# SpaceInvaders-OtherMill-DoubleSided.net
KiCad netlist of a schematic drawn in EAGLE
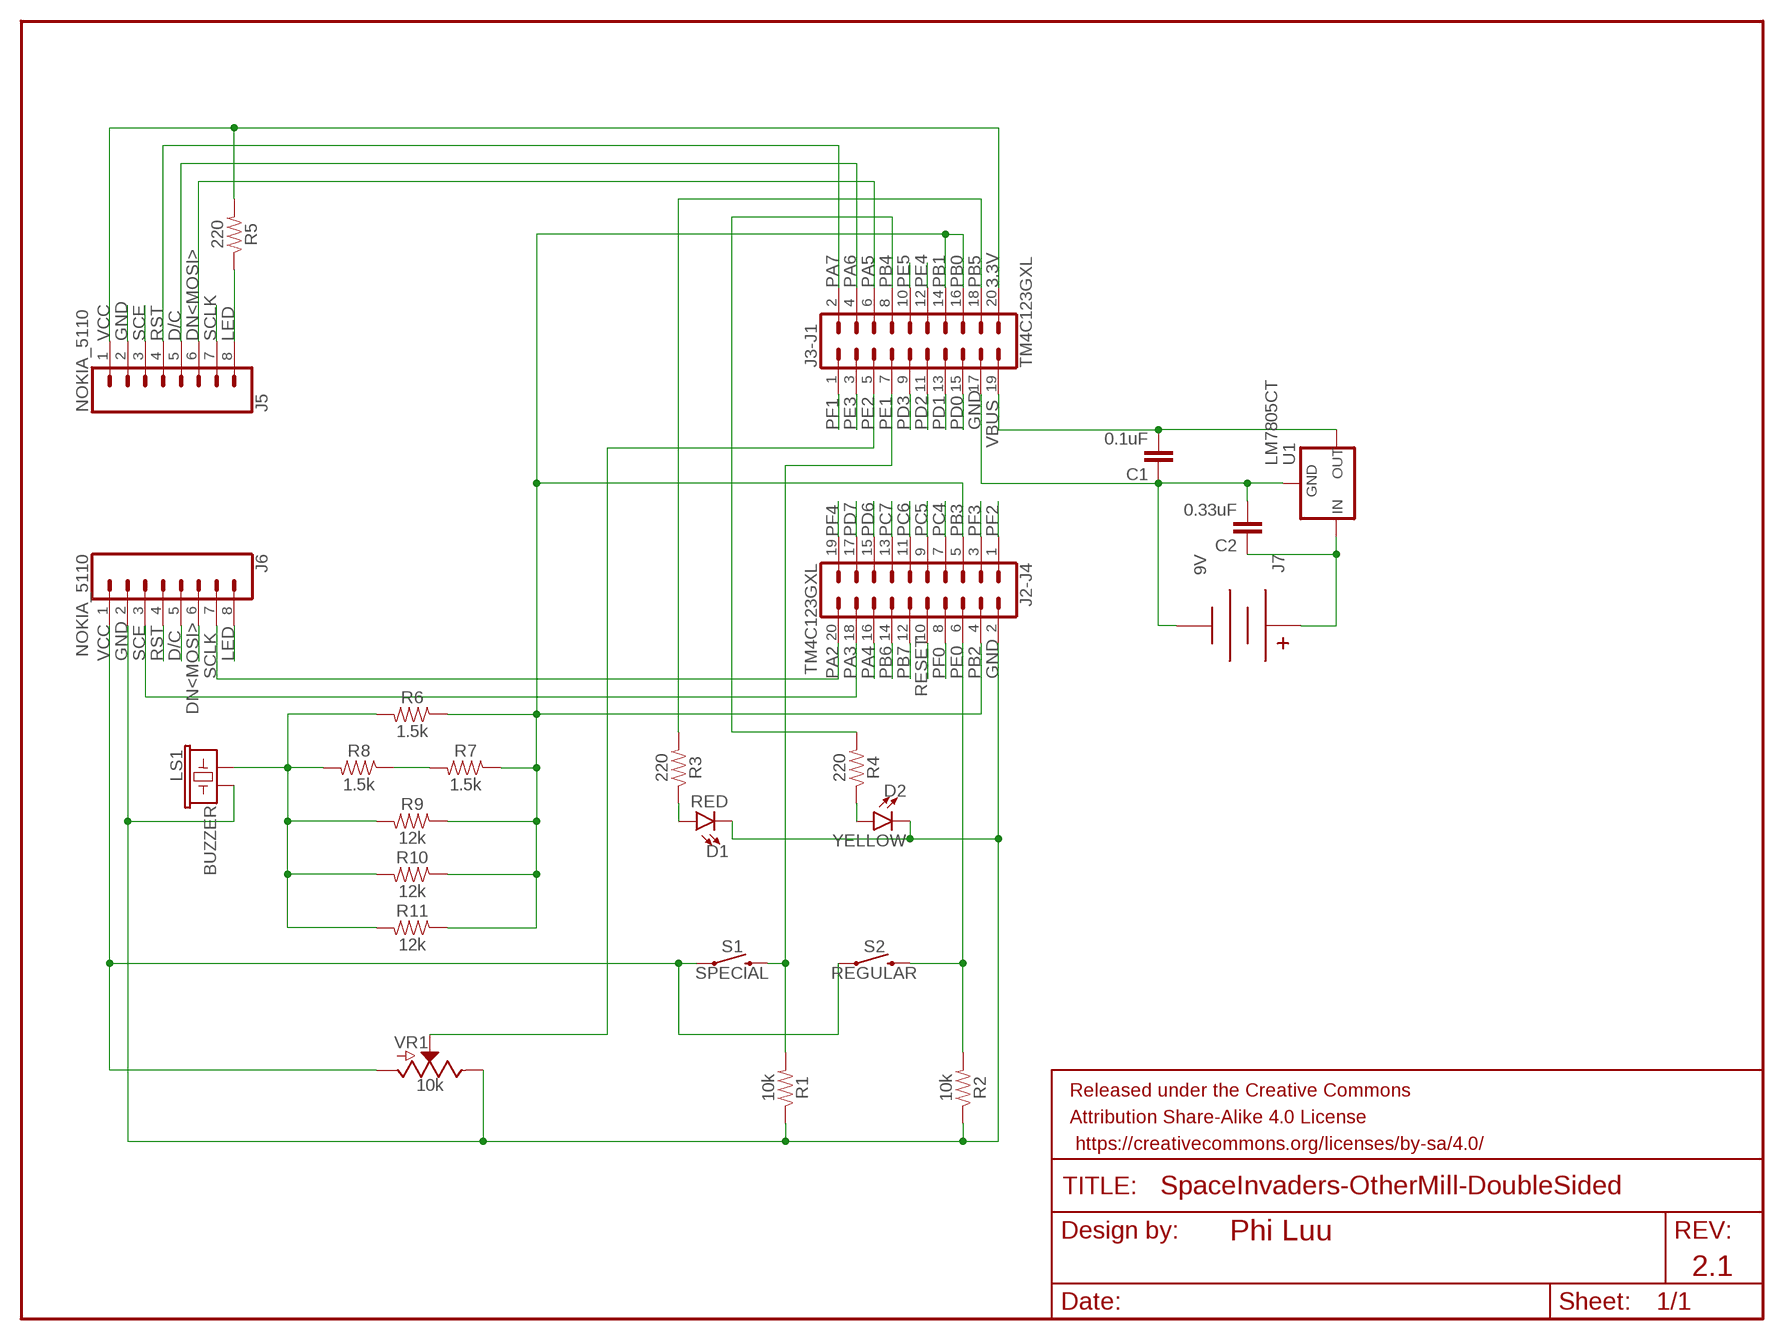
[diagram p0: schematic, sheet 1]

(export (version "E")
  (design (tool "Eeschema 10.0.6"))
  (components
    (comp (ref "C1")
      (value "0.1uF")
      (footprint "eagle-import:CAP-PTH-SMALL-KIT")
      (libsource (lib "eagle-import") (part "0.1UF-KIT-EZ-50V-20%"))
    )
    (comp (ref "C2")
      (value "0.33uF")
      (footprint "eagle-import:CAP-PTH-SMALL-KIT")
      (libsource (lib "eagle-import") (part "0.1UF-KIT-EZ-50V-20%"))
    )
    (comp (ref "D1")
      (value "RED")
      (footprint "eagle-import:LED_5MM")
      (libsource (lib "eagle-import") (part "LED5MM"))
    )
    (comp (ref "D2")
      (value "YELLOW")
      (footprint "eagle-import:LED_5MM")
      (libsource (lib "eagle-import") (part "LED5MM"))
    )
    (comp (ref "FRAME1")
      (value "FRAME-LETTER")
      (footprint "eagle-import:CREATIVE_COMMONS")
      (libsource (lib "eagle-import") (part "FRAME-LETTER"))
    )
    (comp (ref "J2-J4")
      (value "TM4C123GXL")
      (footprint "eagle-import:2X10")
      (libsource (lib "eagle-import") (part "CONN_10X2"))
    )
    (comp (ref "J3-J1")
      (value "TM4C123GXL")
      (footprint "eagle-import:2X10")
      (libsource (lib "eagle-import") (part "CONN_10X2"))
    )
    (comp (ref "J5")
      (value "NOKIA_5110")
      (footprint "eagle-import:1X08")
      (libsource (lib "eagle-import") (part "CONN_08{dblquote}"))
    )
    (comp (ref "J6")
      (value "NOKIA_5110")
      (footprint "eagle-import:1X08")
      (libsource (lib "eagle-import") (part "CONN_08{dblquote}"))
    )
    (comp (ref "J7")
      (value "9V")
      (footprint "eagle-import:BC9VPC")
      (libsource (lib "eagle-import") (part "BC9VPC"))
    )
    (comp (ref "LS1")
      (value "BUZZER")
      (footprint "eagle-import:BUZZER-12MM")
      (libsource (lib "eagle-import") (part "BUZZER-PTH"))
    )
    (comp (ref "R1")
      (value "10k")
      (footprint "eagle-import:AXIAL-0.3")
      (libsource (lib "eagle-import") (part "10KOHM-HORIZ-1/4W-5%"))
    )
    (comp (ref "R2")
      (value "10k")
      (footprint "eagle-import:AXIAL-0.3")
      (libsource (lib "eagle-import") (part "10KOHM-HORIZ-1/4W-5%"))
    )
    (comp (ref "R3")
      (value "220")
      (footprint "eagle-import:AXIAL-0.3")
      (libsource (lib "eagle-import") (part "1KOHM-HORIZ-1/4W-5%"))
    )
    (comp (ref "R4")
      (value "220")
      (footprint "eagle-import:AXIAL-0.3")
      (libsource (lib "eagle-import") (part "1KOHM-HORIZ-1/4W-5%"))
    )
    (comp (ref "R5")
      (value "220")
      (footprint "eagle-import:AXIAL-0.3")
      (libsource (lib "eagle-import") (part "1KOHM-HORIZ-1/4W-5%"))
    )
    (comp (ref "R6")
      (value "1.5k")
      (footprint "eagle-import:AXIAL-0.3")
      (libsource (lib "eagle-import") (part "1KOHM-HORIZ-1/4W-5%"))
    )
    (comp (ref "R7")
      (value "1.5k")
      (footprint "eagle-import:AXIAL-0.3")
      (libsource (lib "eagle-import") (part "1KOHM-HORIZ-1/4W-5%"))
    )
    (comp (ref "R8")
      (value "1.5k")
      (footprint "eagle-import:AXIAL-0.3")
      (libsource (lib "eagle-import") (part "1KOHM-HORIZ-1/4W-5%"))
    )
    (comp (ref "R9")
      (value "12k")
      (footprint "eagle-import:AXIAL-0.3")
      (libsource (lib "eagle-import") (part "1KOHM-HORIZ-1/4W-5%"))
    )
    (comp (ref "R10")
      (value "12k")
      (footprint "eagle-import:AXIAL-0.3")
      (libsource (lib "eagle-import") (part "1KOHM-HORIZ-1/4W-5%"))
    )
    (comp (ref "R11")
      (value "12k")
      (footprint "eagle-import:AXIAL-0.3")
      (libsource (lib "eagle-import") (part "1KOHM-HORIZ-1/4W-5%"))
    )
    (comp (ref "S1")
      (value "SPECIAL")
      (footprint "eagle-import:TACTILE_SWITCH_PTH_6.0MM")
      (libsource (lib "eagle-import") (part "MOMENTARY-SWITCH-SPST-PTH-6.0MM"))
    )
    (comp (ref "S2")
      (value "REGULAR")
      (footprint "eagle-import:TACTILE_SWITCH_PTH_6.0MM")
      (libsource (lib "eagle-import") (part "MOMENTARY-SWITCH-SPST-PTH-6.0MM"))
    )
    (comp (ref "U1")
      (value "LM7805CT")
      (footprint "eagle-import:TO-220-ALT")
      (libsource (lib "eagle-import") (part "V_REG_78XX-TO-220"))
    )
    (comp (ref "VR1")
      (value "10k")
      (footprint "eagle-import:SLIDER-MEDIUM")
      (libsource (lib "eagle-import") (part "POTENTIOMETER_SLIDE-30MM-1/10W-20%"))
    )
  )
  (nets
    (net (code "1") (name "/3.3V") (class "Default")
      (node (ref "J3-J1") (pin "20") (pinfunction "20_20") (pintype "passive"))
      (node (ref "J5") (pin "1") (pinfunction "1_1") (pintype "passive"))
      (node (ref "J6") (pin "1") (pinfunction "1_1") (pintype "passive"))
      (node (ref "R5") (pin "P$2") (pinfunction "2_P$2") (pintype "passive"))
      (node (ref "S1") (pin "1") (pinfunction "1_1") (pintype "passive"))
      (node (ref "S2") (pin "1") (pinfunction "1_1") (pintype "passive"))
      (node (ref "VR1") (pin "BOTTOM") (pinfunction "A_BOTTOM") (pintype "passive"))
    )
    (net (code "2") (name "/GND") (class "Default")
      (node (ref "C1") (pin "1") (pinfunction "1_1") (pintype "passive"))
      (node (ref "C2") (pin "2") (pinfunction "2_2") (pintype "passive"))
      (node (ref "D1") (pin "K") (pinfunction "C_K") (pintype "passive"))
      (node (ref "D2") (pin "K") (pinfunction "C_K") (pintype "passive"))
      (node (ref "J2-J4") (pin "2") (pinfunction "2_2") (pintype "passive"))
      (node (ref "J3-J1") (pin "17") (pinfunction "17_17") (pintype "passive"))
      (node (ref "J5") (pin "2") (pinfunction "2_2") (pintype "passive"))
      (node (ref "J6") (pin "2") (pinfunction "2_2") (pintype "passive"))
      (node (ref "J7") (pin "V-") (pinfunction "V-_V-") (pintype "bidirectional"))
      (node (ref "LS1") (pin "-") (pinfunction "2_-") (pintype "passive"))
      (node (ref "R1") (pin "P$1") (pinfunction "1_P$1") (pintype "passive"))
      (node (ref "R2") (pin "P$1") (pinfunction "1_P$1") (pintype "passive"))
      (node (ref "U1") (pin "GND") (pinfunction "GND_GND") (pintype "input"))
      (node (ref "VR1") (pin "TOP") (pinfunction "E_TOP") (pintype "passive"))
    )
    (net (code "3") (name "/LED") (class "Default")
      (node (ref "J5") (pin "8") (pinfunction "8_8") (pintype "passive"))
      (node (ref "J6") (pin "8") (pinfunction "8_8") (pintype "passive"))
      (node (ref "R5") (pin "P$1") (pinfunction "1_P$1") (pintype "passive"))
    )
    (net (code "4") (name "/PA2") (class "Default")
      (node (ref "J2-J4") (pin "20") (pinfunction "20_20") (pintype "passive"))
      (node (ref "J5") (pin "7") (pinfunction "7_7") (pintype "passive"))
      (node (ref "J6") (pin "7") (pinfunction "7_7") (pintype "passive"))
    )
    (net (code "5") (name "/PA3") (class "Default")
      (node (ref "J2-J4") (pin "18") (pinfunction "18_18") (pintype "passive"))
      (node (ref "J5") (pin "3") (pinfunction "3_3") (pintype "passive"))
      (node (ref "J6") (pin "3") (pinfunction "3_3") (pintype "passive"))
    )
    (net (code "6") (name "/PA4") (class "Default")
      (node (ref "J2-J4") (pin "16") (pinfunction "16_16") (pintype "passive"))
    )
    (net (code "7") (name "/PA5") (class "Default")
      (node (ref "J3-J1") (pin "6") (pinfunction "6_6") (pintype "passive"))
      (node (ref "J5") (pin "6") (pinfunction "6_6") (pintype "passive"))
      (node (ref "J6") (pin "6") (pinfunction "6_6") (pintype "passive"))
    )
    (net (code "8") (name "/PA6") (class "Default")
      (node (ref "J3-J1") (pin "4") (pinfunction "4_4") (pintype "passive"))
      (node (ref "J5") (pin "5") (pinfunction "5_5") (pintype "passive"))
      (node (ref "J6") (pin "5") (pinfunction "5_5") (pintype "passive"))
    )
    (net (code "9") (name "/PA7") (class "Default")
      (node (ref "J3-J1") (pin "2") (pinfunction "2_2") (pintype "passive"))
      (node (ref "J5") (pin "4") (pinfunction "4_4") (pintype "passive"))
      (node (ref "J6") (pin "4") (pinfunction "4_4") (pintype "passive"))
    )
    (net (code "10") (name "/PB4") (class "Default")
      (node (ref "J3-J1") (pin "8") (pinfunction "8_8") (pintype "passive"))
      (node (ref "R4") (pin "P$2") (pinfunction "2_P$2") (pintype "passive"))
    )
    (net (code "11") (name "/PB5") (class "Default")
      (node (ref "J3-J1") (pin "18") (pinfunction "18_18") (pintype "passive"))
      (node (ref "R3") (pin "P$2") (pinfunction "2_P$2") (pintype "passive"))
    )
    (net (code "12") (name "/PB6") (class "Default")
      (node (ref "J2-J4") (pin "14") (pinfunction "14_14") (pintype "passive"))
    )
    (net (code "13") (name "/PB7") (class "Default")
      (node (ref "J2-J4") (pin "12") (pinfunction "12_12") (pintype "passive"))
    )
    (net (code "14") (name "/PC4") (class "Default")
      (node (ref "J2-J4") (pin "7") (pinfunction "7_7") (pintype "passive"))
    )
    (net (code "15") (name "/PC5") (class "Default")
      (node (ref "J2-J4") (pin "9") (pinfunction "9_9") (pintype "passive"))
    )
    (net (code "16") (name "/PC6") (class "Default")
      (node (ref "J2-J4") (pin "11") (pinfunction "11_11") (pintype "passive"))
    )
    (net (code "17") (name "/PC7") (class "Default")
      (node (ref "J2-J4") (pin "13") (pinfunction "13_13") (pintype "passive"))
    )
    (net (code "18") (name "/PD0") (class "Default")
      (node (ref "J3-J1") (pin "15") (pinfunction "15_15") (pintype "passive"))
    )
    (net (code "19") (name "/PD1") (class "Default")
      (node (ref "J3-J1") (pin "13") (pinfunction "13_13") (pintype "passive"))
    )
    (net (code "20") (name "/PD2") (class "Default")
      (node (ref "J3-J1") (pin "11") (pinfunction "11_11") (pintype "passive"))
    )
    (net (code "21") (name "/PD3") (class "Default")
      (node (ref "J3-J1") (pin "9") (pinfunction "9_9") (pintype "passive"))
    )
    (net (code "22") (name "/PD6") (class "Default")
      (node (ref "J2-J4") (pin "15") (pinfunction "15_15") (pintype "passive"))
    )
    (net (code "23") (name "/PD7") (class "Default")
      (node (ref "J2-J4") (pin "17") (pinfunction "17_17") (pintype "passive"))
    )
    (net (code "24") (name "/PE0") (class "Default")
      (node (ref "J2-J4") (pin "6") (pinfunction "6_6") (pintype "passive"))
      (node (ref "R2") (pin "P$2") (pinfunction "2_P$2") (pintype "passive"))
      (node (ref "S2") (pin "3") (pinfunction "2_3") (pintype "passive"))
    )
    (net (code "25") (name "/PE1") (class "Default")
      (node (ref "J3-J1") (pin "7") (pinfunction "7_7") (pintype "passive"))
      (node (ref "R1") (pin "P$2") (pinfunction "2_P$2") (pintype "passive"))
      (node (ref "S1") (pin "3") (pinfunction "2_3") (pintype "passive"))
    )
    (net (code "26") (name "/PE2") (class "Default")
      (node (ref "J3-J1") (pin "5") (pinfunction "5_5") (pintype "passive"))
      (node (ref "VR1") (pin "WIPER") (pinfunction "S_WIPER") (pintype "passive"))
    )
    (net (code "27") (name "/PE3") (class "Default")
      (node (ref "J3-J1") (pin "3") (pinfunction "3_3") (pintype "passive"))
    )
    (net (code "28") (name "/PE4") (class "Default")
      (node (ref "J3-J1") (pin "12") (pinfunction "12_12") (pintype "passive"))
    )
    (net (code "29") (name "/PE5") (class "Default")
      (node (ref "J3-J1") (pin "10") (pinfunction "10_10") (pintype "passive"))
    )
    (net (code "30") (name "/PF0") (class "Default")
      (node (ref "J2-J4") (pin "8") (pinfunction "8_8") (pintype "passive"))
    )
    (net (code "31") (name "/PF1") (class "Default")
      (node (ref "J3-J1") (pin "1") (pinfunction "1_1") (pintype "passive"))
    )
    (net (code "32") (name "/PF2") (class "Default")
      (node (ref "J2-J4") (pin "1") (pinfunction "1_1") (pintype "passive"))
    )
    (net (code "33") (name "/PF3") (class "Default")
      (node (ref "J2-J4") (pin "3") (pinfunction "3_3") (pintype "passive"))
    )
    (net (code "34") (name "/PF4") (class "Default")
      (node (ref "J2-J4") (pin "19") (pinfunction "19_19") (pintype "passive"))
    )
    (net (code "35") (name "/RESET") (class "Default")
      (node (ref "J2-J4") (pin "10") (pinfunction "10_10") (pintype "passive"))
    )
    (net (code "36") (name "/VBUS") (class "Default")
      (node (ref "C1") (pin "2") (pinfunction "2_2") (pintype "passive"))
      (node (ref "J3-J1") (pin "19") (pinfunction "19_19") (pintype "passive"))
      (node (ref "U1") (pin "OUT") (pinfunction "OUT_OUT") (pintype "passive"))
    )
    (net (code "37") (name "Net-(C2-Pad1)") (class "Default")
      (node (ref "C2") (pin "1") (pinfunction "1_1") (pintype "passive"))
      (node (ref "J7") (pin "V+") (pinfunction "V+_V+") (pintype "bidirectional"))
      (node (ref "U1") (pin "IN") (pinfunction "IN_IN") (pintype "input"))
    )
    (net (code "38") (name "Net-(LS1-1)") (class "Default")
      (node (ref "LS1") (pin "+") (pinfunction "1_+") (pintype "passive"))
      (node (ref "R10") (pin "P$2") (pinfunction "2_P$2") (pintype "passive"))
      (node (ref "R11") (pin "P$2") (pinfunction "2_P$2") (pintype "passive"))
      (node (ref "R6") (pin "P$2") (pinfunction "2_P$2") (pintype "passive"))
      (node (ref "R8") (pin "P$2") (pinfunction "2_P$2") (pintype "passive"))
      (node (ref "R9") (pin "P$2") (pinfunction "2_P$2") (pintype "passive"))
    )
    (net (code "39") (name "Net-(R3-1)") (class "Default")
      (node (ref "D1") (pin "A") (pinfunction "A_A") (pintype "passive"))
      (node (ref "R3") (pin "P$1") (pinfunction "1_P$1") (pintype "passive"))
    )
    (net (code "40") (name "Net-(R4-1)") (class "Default")
      (node (ref "D2") (pin "A") (pinfunction "A_A") (pintype "passive"))
      (node (ref "R4") (pin "P$1") (pinfunction "1_P$1") (pintype "passive"))
    )
    (net (code "41") (name "Net-(R7-2)") (class "Default")
      (node (ref "R7") (pin "P$2") (pinfunction "2_P$2") (pintype "passive"))
      (node (ref "R8") (pin "P$1") (pinfunction "1_P$1") (pintype "passive"))
    )
    (net (code "42") (name "Net-(R10-1)") (class "Default")
      (node (ref "J2-J4") (pin "4") (pinfunction "4_4") (pintype "passive"))
      (node (ref "J2-J4") (pin "5") (pinfunction "5_5") (pintype "passive"))
      (node (ref "J3-J1") (pin "14") (pinfunction "14_14") (pintype "passive"))
      (node (ref "J3-J1") (pin "16") (pinfunction "16_16") (pintype "passive"))
      (node (ref "R10") (pin "P$1") (pinfunction "1_P$1") (pintype "passive"))
      (node (ref "R11") (pin "P$1") (pinfunction "1_P$1") (pintype "passive"))
      (node (ref "R6") (pin "P$1") (pinfunction "1_P$1") (pintype "passive"))
      (node (ref "R7") (pin "P$1") (pinfunction "1_P$1") (pintype "passive"))
      (node (ref "R9") (pin "P$1") (pinfunction "1_P$1") (pintype "passive"))
    )
  )
)
